# main.net
KiCad netlist of a schematic drawn in Altium Designer
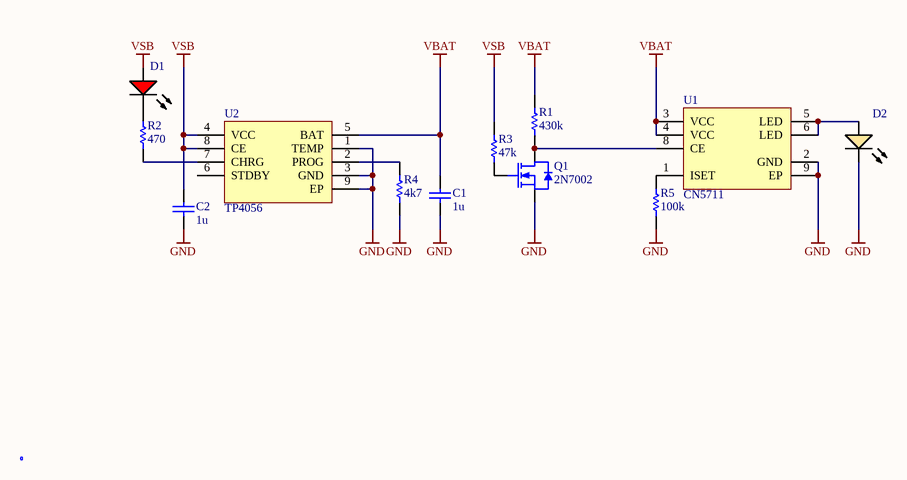
[diagram p0: main.SchDoc]

(export (version "E")
  (design (tool "Eeschema 10.0.6"))
  (components
    (comp (ref "C1") (value "1u") (footprint "C1206") (libsource (lib "Miscellaneous Devices") (part "Cap")))
    (comp (ref "C2") (value "1u") (footprint "C1206") (libsource (lib "Miscellaneous Devices") (part "Cap")))
    (comp (ref "D1")
      (value "RED")
      (footprint "LED-0603-RED")
      (description "LED 0603 RED")
      (libsource (lib "Miscellaneous Devices") (part "LED-0603-RED"))
    )
    (comp (ref "D2")
      (value "RED")
      (footprint "LED-1W")
      (description "LED 0603 RED")
      (libsource (lib "Schlib2") (part "LED-0603-RED"))
    )
    (comp (ref "LOGO1") (value "LOGO") (footprint "LOGO") (libsource (lib "Schlib1") (part "LOGO")))
    (comp (ref "Q1")
      (value "2N7002")
      (footprint "SOT-23")
      (libsource (lib "Miscellaneous Devices") (part "2N7002"))
    )
    (comp (ref "R1")
      (value "430k")
      (footprint "R0603")
      (libsource (lib "Miscellaneous Devices") (part "Res1"))
    )
    (comp (ref "R2")
      (value "470")
      (footprint "R0603")
      (libsource (lib "Miscellaneous Devices") (part "Res1"))
    )
    (comp (ref "R3")
      (value "47k")
      (footprint "R0603")
      (libsource (lib "Miscellaneous Devices") (part "Res1"))
    )
    (comp (ref "R4")
      (value "4k7")
      (footprint "R0603")
      (libsource (lib "Miscellaneous Devices") (part "Res1"))
    )
    (comp (ref "R5")
      (value "100k")
      (footprint "R0603")
      (libsource (lib "Miscellaneous Devices") (part "Res1"))
    )
    (comp (ref "U1") (value "CN5711") (footprint "PowerSOIC-8") (libsource (lib "Schlib2") (part "CN5711")))
    (comp (ref "U2") (value "TP4056") (footprint "PowerSOIC-8") (libsource (lib "Schlib1") (part "TP4056")))
  )
  (nets
    (net (code "1") (name "GND") (class "Default")
      (node (ref "C1") (pin "1") (pinfunction "1_1") (pintype "passive"))
      (node (ref "C2") (pin "1") (pinfunction "1_1") (pintype "passive"))
      (node (ref "D2") (pin "2") (pinfunction "K_2") (pintype "passive"))
      (node (ref "Q1") (pin "2") (pinfunction "SOURCE_2") (pintype "passive"))
      (node (ref "R4") (pin "1") (pinfunction "1_1") (pintype "passive"))
      (node (ref "R5") (pin "1") (pinfunction "1_1") (pintype "passive"))
      (node (ref "U1") (pin "2") (pinfunction "GND_2") (pintype "passive"))
      (node (ref "U1") (pin "9") (pinfunction "EP_9") (pintype "passive"))
      (node (ref "U2") (pin "1") (pinfunction "TEMP_1") (pintype "passive"))
      (node (ref "U2") (pin "3") (pinfunction "GND_3") (pintype "passive"))
      (node (ref "U2") (pin "9") (pinfunction "EP_9") (pintype "passive"))
    )
    (net (code "2") (name "Net-(D1-K)") (class "Default")
      (node (ref "D1") (pin "2") (pinfunction "K_2") (pintype "passive"))
      (node (ref "R2") (pin "2") (pinfunction "2_2") (pintype "passive"))
    )
    (net (code "3") (name "Net-(D2-A)") (class "Default")
      (node (ref "D2") (pin "1") (pinfunction "A_1") (pintype "passive"))
      (node (ref "U1") (pin "5") (pinfunction "LED_5") (pintype "passive"))
      (node (ref "U1") (pin "6") (pinfunction "LED_6") (pintype "passive"))
    )
    (net (code "4") (name "Net-(Q1-DRAIN)") (class "Default")
      (node (ref "Q1") (pin "3") (pinfunction "DRAIN_3") (pintype "passive"))
      (node (ref "R1") (pin "2") (pinfunction "2_2") (pintype "passive"))
      (node (ref "U1") (pin "8") (pinfunction "CE_8") (pintype "passive"))
    )
    (net (code "5") (name "Net-(Q1-GATE)") (class "Default")
      (node (ref "Q1") (pin "1") (pinfunction "GATE_1") (pintype "passive"))
      (node (ref "R3") (pin "2") (pinfunction "2_2") (pintype "passive"))
    )
    (net (code "6") (name "Net-(U1-ISET)") (class "Default")
      (node (ref "R5") (pin "2") (pinfunction "2_2") (pintype "passive"))
      (node (ref "U1") (pin "1") (pinfunction "ISET_1") (pintype "passive"))
    )
    (net (code "7") (name "Net-(U2-CHRG)") (class "Default")
      (node (ref "R2") (pin "1") (pinfunction "1_1") (pintype "passive"))
      (node (ref "U2") (pin "7") (pinfunction "CHRG_7") (pintype "passive"))
    )
    (net (code "8") (name "Net-(U2-PROG)") (class "Default")
      (node (ref "R4") (pin "2") (pinfunction "2_2") (pintype "passive"))
      (node (ref "U2") (pin "2") (pinfunction "PROG_2") (pintype "passive"))
    )
    (net (code "9") (name "VBAT") (class "Default")
      (node (ref "C1") (pin "2") (pinfunction "2_2") (pintype "passive"))
      (node (ref "R1") (pin "1") (pinfunction "1_1") (pintype "passive"))
      (node (ref "U1") (pin "3") (pinfunction "VCC_3") (pintype "passive"))
      (node (ref "U1") (pin "4") (pinfunction "VCC_4") (pintype "passive"))
      (node (ref "U2") (pin "5") (pinfunction "BAT_5") (pintype "passive"))
    )
    (net (code "10") (name "VSB") (class "Default")
      (node (ref "C2") (pin "2") (pinfunction "2_2") (pintype "passive"))
      (node (ref "D1") (pin "1") (pinfunction "A_1") (pintype "passive"))
      (node (ref "R3") (pin "1") (pinfunction "1_1") (pintype "passive"))
      (node (ref "U2") (pin "4") (pinfunction "VCC_4") (pintype "passive"))
      (node (ref "U2") (pin "8") (pinfunction "CE_8") (pintype "passive"))
    )
    (net (code "11") (name "unconnected-(U2-STDBY-Pad6)") (class "Default")
      (node (ref "U2") (pin "6") (pinfunction "STDBY_6") (pintype "passive"))
    )
  )
)
